# ETHERNET.net
KiCad netlist of a schematic drawn in Altium Designer
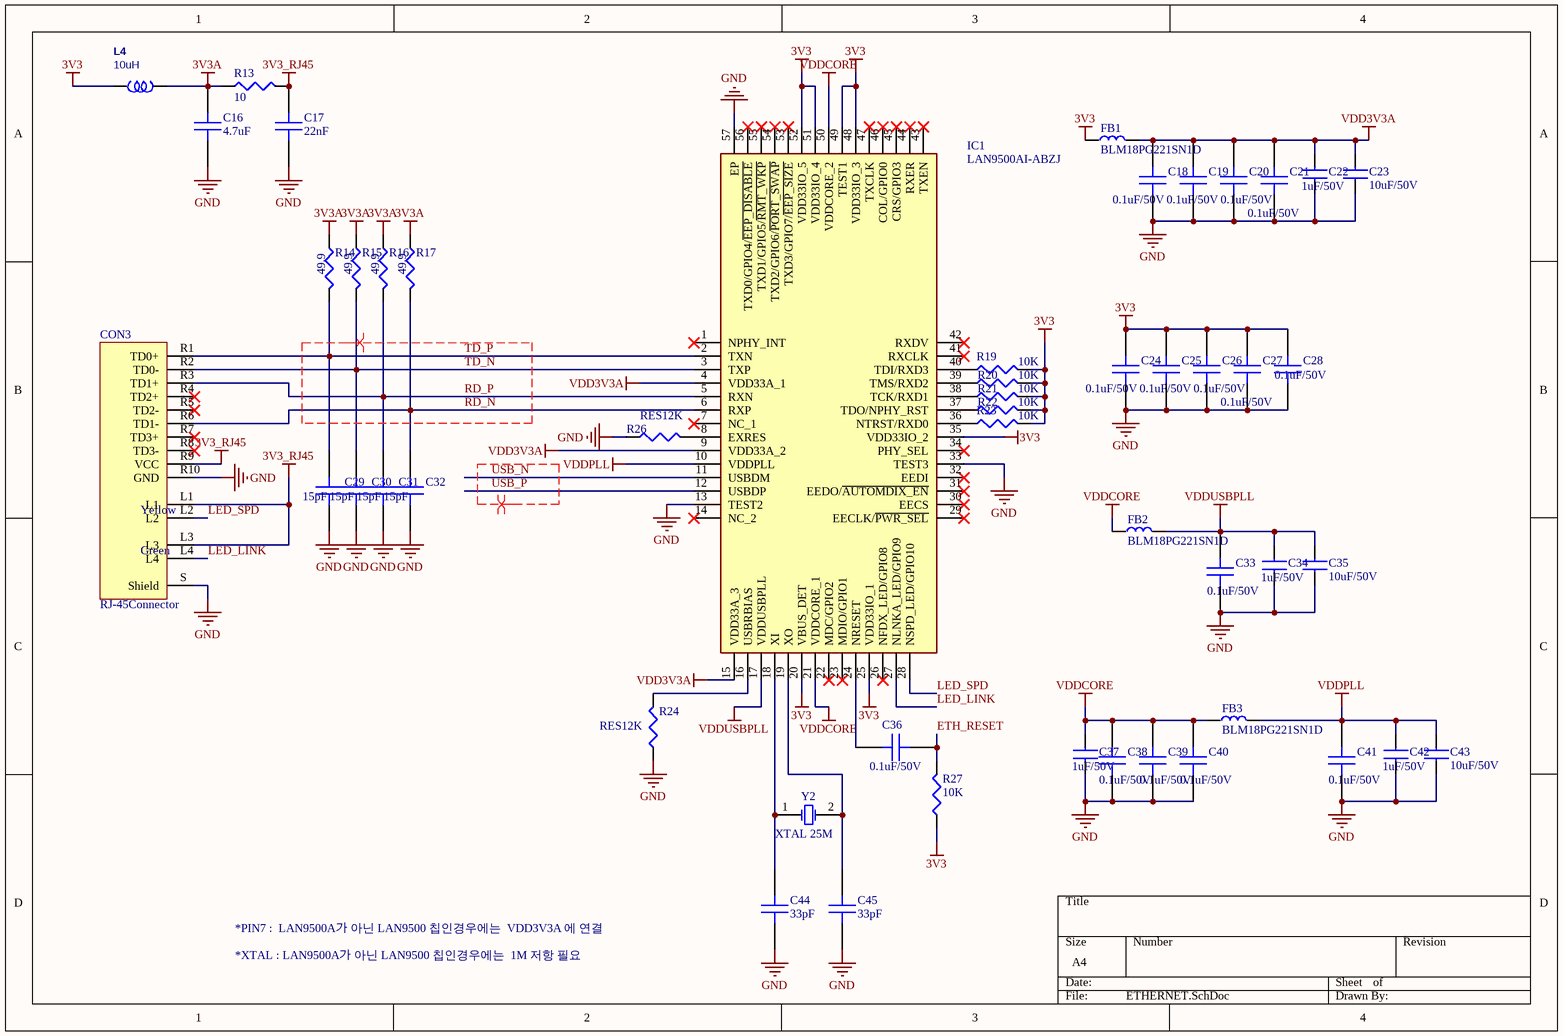
[diagram p0: ETHERNET.SchDoc]

(export (version "E")
  (design (tool "Eeschema 10.0.6"))
  (components
    (comp (ref "C16")
      (value "4.7uF")
      (footprint "CAP2.2u_0603")
      (description "CAP4.7u_0603")
      (libsource (lib "SensoMonitor") (part "CAP2.2u_0603"))
    )
    (comp (ref "C17")
      (value "22nF")
      (footprint "CAP2.2u_0603")
      (description "CAP22n_0603")
      (libsource (lib "SensoMonitor") (part "CAP2.2u_0603"))
    )
    (comp (ref "C18")
      (value "0.1uF/50V")
      (footprint "CAP0.1u_0603_ceramic")
      (description "cap, 0.1u 0603, 50V")
      (libsource (lib "MyLIB240624") (part "CAP0.1u_0603_ceramic"))
    )
    (comp (ref "C19")
      (value "0.1uF/50V")
      (footprint "CAP0.1u_0603_ceramic")
      (description "cap, 0.1u 0603, 50V")
      (libsource (lib "MyLIB240624") (part "CAP0.1u_0603_ceramic"))
    )
    (comp (ref "C20")
      (value "0.1uF/50V")
      (footprint "CAP0.1u_0603_ceramic")
      (description "cap, 0.1u 0603, 50V")
      (libsource (lib "MyLIB240624") (part "CAP0.1u_0603_ceramic"))
    )
    (comp (ref "C21")
      (value "0.1uF/50V")
      (footprint "CAP0.1u_0603_ceramic")
      (description "cap, 0.1u 0603, 50V")
      (libsource (lib "MyLIB240624") (part "CAP0.1u_0603_ceramic"))
    )
    (comp (ref "C22")
      (value "1uF/50V")
      (footprint "C-2012")
      (description "Capacitor, ceramic, 50V, 0805")
      (libsource (lib "MyLIB240624") (part "Cap1_1"))
    )
    (comp (ref "C23")
      (value "10uF/50V")
      (footprint "C-2012")
      (description "Capacitor, ceramic, 50V, 1206")
      (libsource (lib "MyLIB240624") (part "Cap1_1"))
    )
    (comp (ref "C24")
      (value "0.1uF/50V")
      (footprint "CAP0.1u_0603_ceramic")
      (description "cap, 0.1u 0603, 50V")
      (libsource (lib "MyLIB240624") (part "CAP0.1u_0603_ceramic"))
    )
    (comp (ref "C25")
      (value "0.1uF/50V")
      (footprint "CAP0.1u_0603_ceramic")
      (description "cap, 0.1u 0603, 50V")
      (libsource (lib "MyLIB240624") (part "CAP0.1u_0603_ceramic"))
    )
    (comp (ref "C26")
      (value "0.1uF/50V")
      (footprint "CAP0.1u_0603_ceramic")
      (description "cap, 0.1u 0603, 50V")
      (libsource (lib "MyLIB240624") (part "CAP0.1u_0603_ceramic"))
    )
    (comp (ref "C27")
      (value "0.1uF/50V")
      (footprint "CAP0.1u_0603_ceramic")
      (description "cap, 0.1u 0603, 50V")
      (libsource (lib "MyLIB240624") (part "CAP0.1u_0603_ceramic"))
    )
    (comp (ref "C28")
      (value "0.1uF/50V")
      (footprint "CAP0.1u_0603_ceramic")
      (description "cap, 0.1u 0603, 50V")
      (libsource (lib "MyLIB240624") (part "CAP0.1u_0603_ceramic"))
    )
    (comp (ref "C29")
      (value "15pF")
      (footprint "CAP2.2u_0603")
      (description "CAP15pF_0603")
      (libsource (lib "SensoMonitor") (part "CAP2.2u_0603"))
    )
    (comp (ref "C30")
      (value "15pF")
      (footprint "CAP2.2u_0603")
      (description "CAP15pF_0603")
      (libsource (lib "SensoMonitor") (part "CAP2.2u_0603"))
    )
    (comp (ref "C31")
      (value "15pF")
      (footprint "CAP2.2u_0603")
      (description "CAP15pF_0603")
      (libsource (lib "SensoMonitor") (part "CAP2.2u_0603"))
    )
    (comp (ref "C32")
      (value "15pF")
      (footprint "CAP2.2u_0603")
      (description "CAP15pF_0603")
      (libsource (lib "SensoMonitor") (part "CAP2.2u_0603"))
    )
    (comp (ref "C33")
      (value "0.1uF/50V")
      (footprint "CAP0.1u_0603_ceramic")
      (description "cap, 0.1u 0603, 50V")
      (libsource (lib "MyLIB240624") (part "CAP0.1u_0603_ceramic"))
    )
    (comp (ref "C34")
      (value "1uF/50V")
      (footprint "C-2012")
      (description "Capacitor, ceramic, 50V, 0805")
      (libsource (lib "MyLIB240624") (part "Cap1_1"))
    )
    (comp (ref "C35")
      (value "10uF/50V")
      (footprint "C-2012")
      (description "Capacitor, ceramic, 50V, 1206")
      (libsource (lib "MyLIB240624") (part "Cap1_1"))
    )
    (comp (ref "C36")
      (value "0.1uF/50V")
      (footprint "CAP0.1u_0603_ceramic")
      (description "cap, 0.1u 0603, 50V")
      (libsource (lib "MyLIB240624") (part "CAP0.1u_0603_ceramic"))
    )
    (comp (ref "C37")
      (value "1uF/50V")
      (footprint "C-2012")
      (description "Capacitor, ceramic, 50V, 0805")
      (libsource (lib "MyLIB240624") (part "Cap1_1"))
    )
    (comp (ref "C38")
      (value "0.1uF/50V")
      (footprint "CAP0.1u_0603_ceramic")
      (description "cap, 0.1u 0603, 50V")
      (libsource (lib "MyLIB240624") (part "CAP0.1u_0603_ceramic"))
    )
    (comp (ref "C39")
      (value "0.1uF/50V")
      (footprint "CAP0.1u_0603_ceramic")
      (description "cap, 0.1u 0603, 50V")
      (libsource (lib "MyLIB240624") (part "CAP0.1u_0603_ceramic"))
    )
    (comp (ref "C40")
      (value "0.1uF/50V")
      (footprint "CAP0.1u_0603_ceramic")
      (description "cap, 0.1u 0603, 50V")
      (libsource (lib "MyLIB240624") (part "CAP0.1u_0603_ceramic"))
    )
    (comp (ref "C41")
      (value "0.1uF/50V")
      (footprint "CAP0.1u_0603_ceramic")
      (description "cap, 0.1u 0603, 50V")
      (libsource (lib "MyLIB240624") (part "CAP0.1u_0603_ceramic"))
    )
    (comp (ref "C42")
      (value "1uF/50V")
      (footprint "C-2012")
      (description "Capacitor, ceramic, 50V, 0805")
      (libsource (lib "MyLIB240624") (part "Cap1_1"))
    )
    (comp (ref "C43")
      (value "10uF/50V")
      (footprint "C-2012")
      (description "Capacitor, ceramic, 50V, 1206")
      (libsource (lib "MyLIB240624") (part "Cap1_1"))
    )
    (comp (ref "C44")
      (value "33pF")
      (footprint "CAP33p_0603")
      (description "CAP33p_0603,ceramic")
      (libsource (lib "SensoMonitor") (part "CAP33p_0603"))
    )
    (comp (ref "C45")
      (value "33pF")
      (footprint "CAP33p_0603")
      (description "CAP33p_0603,ceramic")
      (libsource (lib "SensoMonitor") (part "CAP33p_0603"))
    )
    (comp (ref "CON3")
      (value "RJ-45Connector")
      (footprint "[RJ45]24G-1835GYD2NL")
      (description "[RJ-45] 24G-1835GYD2NL")
      (libsource (lib "SensoMonitor") (part "[RJ45]24G-1835GYD2NL"))
    )
    (comp (ref "FB1")
      (value "BLM18PG221SN1D")
      (footprint "BLM18PG221SN1D")
      (description "Ferrite Bead, BLM18PG221SN1D, 0603")
      (fields (field (name "MOUSER PART NUMBER") "81-BLM18PG221SN1D"))
      (libsource (lib "SensoMonitor") (part "BLM18PG221SN1D"))
    )
    (comp (ref "FB2")
      (value "BLM18PG221SN1D")
      (footprint "BLM18PG221SN1D")
      (description "Ferrite Bead, BLM18PG221SN1D, 0603")
      (fields (field (name "MOUSER PART NUMBER") "81-BLM18PG221SN1D"))
      (libsource (lib "SensoMonitor") (part "BLM18PG221SN1D"))
    )
    (comp (ref "FB3")
      (value "BLM18PG221SN1D")
      (footprint "BLM18PG221SN1D")
      (description "Ferrite Bead, BLM18PG221SN1D, 0603")
      (fields (field (name "MOUSER PART NUMBER") "81-BLM18PG221SN1D"))
      (libsource (lib "SensoMonitor") (part "BLM18PG221SN1D"))
    )
    (comp (ref "IC1")
      (value "LAN9500AI-ABZJ")
      (footprint "LAN9500AI-ABZJ")
      (description "Integrated Circuit, LAN9500AI-ABZJ, Microchip")
      (fields (field (name "MOUSER PART NUMBER") "886-LAN9500AI-ABZJ"))
      (libsource (lib "SensoMonitor") (part "LAN9500AI-ABZJ"))
    )
    (comp (ref "L4")
      (value "10uH")
      (footprint "IND10uCoil")
      (description "10uH(2012)")
      (libsource (lib "SensoMonitor") (part "IND10uCoil"))
    )
    (comp (ref "R13")
      (value "10")
      (footprint "RES20K_0603")
      (description "RES10_0603")
      (libsource (lib "SensoMonitor") (part "RES20K"))
    )
    (comp (ref "R14")
      (value "49.9")
      (footprint "RES20K_0603")
      (description "RES49.9_0603")
      (libsource (lib "SensoMonitor") (part "RES20K"))
    )
    (comp (ref "R15")
      (value "49.9")
      (footprint "RES20K_0603")
      (description "RES49.9_0603")
      (libsource (lib "SensoMonitor") (part "RES20K"))
    )
    (comp (ref "R16")
      (value "49.9")
      (footprint "RES20K_0603")
      (description "RES49.9_0603")
      (libsource (lib "SensoMonitor") (part "RES20K"))
    )
    (comp (ref "R17")
      (value "49.9")
      (footprint "RES20K_0603")
      (description "RES49.9_0603")
      (libsource (lib "SensoMonitor") (part "RES20K"))
    )
    (comp (ref "R19")
      (value "10K")
      (footprint "RES20K_0603")
      (description "RES10K_0603")
      (libsource (lib "SensoMonitor") (part "RES20K"))
    )
    (comp (ref "R20")
      (value "10K")
      (footprint "RES20K_0603")
      (description "RES10K_0603")
      (libsource (lib "SensoMonitor") (part "RES20K"))
    )
    (comp (ref "R21")
      (value "10K")
      (footprint "RES20K_0603")
      (description "RES10K_0603")
      (libsource (lib "SensoMonitor") (part "RES20K"))
    )
    (comp (ref "R22")
      (value "10K")
      (footprint "RES20K_0603")
      (description "RES10K_0603")
      (libsource (lib "SensoMonitor") (part "RES20K"))
    )
    (comp (ref "R23")
      (value "10K")
      (footprint "RES20K_0603")
      (description "RES10K_0603")
      (libsource (lib "SensoMonitor") (part "RES20K"))
    )
    (comp (ref "R24")
      (value "RES12K")
      (footprint "RES20K_0603")
      (description "RES12K_0603,1%")
      (libsource (lib "SensoMonitor") (part "RES20K"))
    )
    (comp (ref "R26")
      (value "RES12K")
      (footprint "RES20K_0603")
      (description "RES12K_0603,1%")
      (libsource (lib "SensoMonitor") (part "RES20K"))
    )
    (comp (ref "R27")
      (value "10K")
      (footprint "RES20K_0603")
      (description "RES10K_0603")
      (libsource (lib "SensoMonitor") (part "RES20K"))
    )
    (comp (ref "Y2")
      (value "XTAL 25M")
      (footprint "XTAL_SMD_8M")
      (libsource (lib "MyLIB240624") (part "XTAL8M"))
    )
  )
  (nets
    (net (code "1") (name "/ETH_RESET") (class "Default")
      (node (ref "C36") (pin "1") (pinfunction "1_1") (pintype "passive"))
      (node (ref "R27") (pin "2") (pinfunction "2_2") (pintype "passive"))
    )
    (net (code "2") (name "/LED_LINK") (class "Default")
      (node (ref "CON3") (pin "L4") (pinfunction "L4_L4") (pintype "passive"))
      (node (ref "IC1") (pin "27") (pinfunction "NLNKA_LED/GPIO9_27") (pintype "passive"))
    )
    (net (code "3") (name "/LED_SPD") (class "Default")
      (node (ref "CON3") (pin "L2") (pinfunction "L2_L2") (pintype "passive"))
      (node (ref "IC1") (pin "28") (pinfunction "NSPD_LED/GPIO10_28") (pintype "passive"))
    )
    (net (code "4") (name "/RD_N") (class "Default")
      (node (ref "C32") (pin "2") (pinfunction "2_2") (pintype "passive"))
      (node (ref "CON3") (pin "R6") (pinfunction "TD1-_R6") (pintype "passive"))
      (node (ref "IC1") (pin "6") (pinfunction "RXP_6") (pintype "passive"))
      (node (ref "R17") (pin "2") (pinfunction "2_2") (pintype "passive"))
    )
    (net (code "5") (name "/RD_P") (class "Default")
      (node (ref "C31") (pin "2") (pinfunction "2_2") (pintype "passive"))
      (node (ref "CON3") (pin "R3") (pinfunction "TD1+_R3") (pintype "passive"))
      (node (ref "IC1") (pin "5") (pinfunction "RXN_5") (pintype "passive"))
      (node (ref "R16") (pin "2") (pinfunction "2_2") (pintype "passive"))
    )
    (net (code "6") (name "/TD_N") (class "Default")
      (node (ref "C30") (pin "2") (pinfunction "2_2") (pintype "passive"))
      (node (ref "CON3") (pin "R2") (pinfunction "TD0-_R2") (pintype "passive"))
      (node (ref "IC1") (pin "3") (pinfunction "TXP_3") (pintype "passive"))
      (node (ref "R15") (pin "2") (pinfunction "2_2") (pintype "passive"))
    )
    (net (code "7") (name "/TD_P") (class "Default")
      (node (ref "C29") (pin "2") (pinfunction "2_2") (pintype "passive"))
      (node (ref "CON3") (pin "R1") (pinfunction "TD0+_R1") (pintype "passive"))
      (node (ref "IC1") (pin "2") (pinfunction "TXN_2") (pintype "passive"))
      (node (ref "R14") (pin "2") (pinfunction "2_2") (pintype "passive"))
    )
    (net (code "8") (name "/USB_N") (class "Default")
      (node (ref "IC1") (pin "11") (pinfunction "USBDM_11") (pintype "passive"))
    )
    (net (code "9") (name "/USB_P") (class "Default")
      (node (ref "IC1") (pin "12") (pinfunction "USBDP_12") (pintype "passive"))
    )
    (net (code "10") (name "3V3") (class "Default")
      (node (ref "C24") (pin "2") (pinfunction "2_2") (pintype "passive"))
      (node (ref "C25") (pin "2") (pinfunction "2_2") (pintype "passive"))
      (node (ref "C26") (pin "2") (pinfunction "2_2") (pintype "passive"))
      (node (ref "C27") (pin "2") (pinfunction "2_2") (pintype "passive"))
      (node (ref "C28") (pin "2") (pinfunction "2_2") (pintype "passive"))
      (node (ref "FB1") (pin "1") (pinfunction "1_1") (pintype "passive"))
      (node (ref "IC1") (pin "20") (pinfunction "VBUS_DET_20") (pintype "passive"))
      (node (ref "IC1") (pin "25") (pinfunction "VDD33IO_1_25") (pintype "passive"))
      (node (ref "IC1") (pin "35") (pinfunction "VDD33IO_2_35") (pintype "passive"))
      (node (ref "IC1") (pin "48") (pinfunction "VDD33IO_3_48") (pintype "passive"))
      (node (ref "IC1") (pin "49") (pinfunction "TEST1_49") (pintype "passive"))
      (node (ref "IC1") (pin "51") (pinfunction "VDD33IO_4_51") (pintype "passive"))
      (node (ref "IC1") (pin "52") (pinfunction "VDD33IO_5_52") (pintype "passive"))
      (node (ref "L4") (pin "2") (pintype "passive"))
      (node (ref "R19") (pin "2") (pinfunction "2_2") (pintype "passive"))
      (node (ref "R20") (pin "2") (pinfunction "2_2") (pintype "passive"))
      (node (ref "R21") (pin "2") (pinfunction "2_2") (pintype "passive"))
      (node (ref "R22") (pin "2") (pinfunction "2_2") (pintype "passive"))
      (node (ref "R23") (pin "2") (pinfunction "2_2") (pintype "passive"))
      (node (ref "R27") (pin "1") (pinfunction "1_1") (pintype "passive"))
    )
    (net (code "11") (name "3V3A") (class "Default")
      (node (ref "C16") (pin "2") (pinfunction "2_2") (pintype "passive"))
      (node (ref "L4") (pin "1") (pintype "passive"))
      (node (ref "R13") (pin "1") (pinfunction "1_1") (pintype "passive"))
      (node (ref "R14") (pin "1") (pinfunction "1_1") (pintype "passive"))
      (node (ref "R15") (pin "1") (pinfunction "1_1") (pintype "passive"))
      (node (ref "R16") (pin "1") (pinfunction "1_1") (pintype "passive"))
      (node (ref "R17") (pin "1") (pinfunction "1_1") (pintype "passive"))
    )
    (net (code "12") (name "3V3_RJ45") (class "Default")
      (node (ref "C17") (pin "2") (pinfunction "2_2") (pintype "passive"))
      (node (ref "CON3") (pin "L1") (pinfunction "L1_L1") (pintype "passive"))
      (node (ref "CON3") (pin "L3") (pinfunction "L3_L3") (pintype "passive"))
      (node (ref "CON3") (pin "R9") (pinfunction "VCC_R9") (pintype "passive"))
      (node (ref "R13") (pin "2") (pinfunction "2_2") (pintype "passive"))
    )
    (net (code "13") (name "GND") (class "Default")
      (node (ref "C16") (pin "1") (pinfunction "1_1") (pintype "passive"))
      (node (ref "C17") (pin "1") (pinfunction "1_1") (pintype "passive"))
      (node (ref "C18") (pin "1") (pinfunction "1_1") (pintype "passive"))
      (node (ref "C19") (pin "1") (pinfunction "1_1") (pintype "passive"))
      (node (ref "C20") (pin "1") (pinfunction "1_1") (pintype "passive"))
      (node (ref "C21") (pin "1") (pinfunction "1_1") (pintype "passive"))
      (node (ref "C22") (pin "2") (pintype "passive"))
      (node (ref "C23") (pin "2") (pintype "passive"))
      (node (ref "C24") (pin "1") (pinfunction "1_1") (pintype "passive"))
      (node (ref "C25") (pin "1") (pinfunction "1_1") (pintype "passive"))
      (node (ref "C26") (pin "1") (pinfunction "1_1") (pintype "passive"))
      (node (ref "C27") (pin "1") (pinfunction "1_1") (pintype "passive"))
      (node (ref "C28") (pin "1") (pinfunction "1_1") (pintype "passive"))
      (node (ref "C29") (pin "1") (pinfunction "1_1") (pintype "passive"))
      (node (ref "C30") (pin "1") (pinfunction "1_1") (pintype "passive"))
      (node (ref "C31") (pin "1") (pinfunction "1_1") (pintype "passive"))
      (node (ref "C32") (pin "1") (pinfunction "1_1") (pintype "passive"))
      (node (ref "C33") (pin "1") (pinfunction "1_1") (pintype "passive"))
      (node (ref "C34") (pin "2") (pintype "passive"))
      (node (ref "C35") (pin "2") (pintype "passive"))
      (node (ref "C37") (pin "2") (pintype "passive"))
      (node (ref "C38") (pin "1") (pinfunction "1_1") (pintype "passive"))
      (node (ref "C39") (pin "1") (pinfunction "1_1") (pintype "passive"))
      (node (ref "C40") (pin "1") (pinfunction "1_1") (pintype "passive"))
      (node (ref "C41") (pin "1") (pinfunction "1_1") (pintype "passive"))
      (node (ref "C42") (pin "2") (pintype "passive"))
      (node (ref "C43") (pin "2") (pintype "passive"))
      (node (ref "C44") (pin "1") (pinfunction "1_1") (pintype "passive"))
      (node (ref "C45") (pin "1") (pinfunction "1_1") (pintype "passive"))
      (node (ref "CON3") (pin "R10") (pinfunction "GND_R10") (pintype "passive"))
      (node (ref "CON3") (pin "S") (pinfunction "Shield_S") (pintype "passive"))
      (node (ref "IC1") (pin "13") (pinfunction "TEST2_13") (pintype "passive"))
      (node (ref "IC1") (pin "33") (pinfunction "TEST3_33") (pintype "passive"))
      (node (ref "IC1") (pin "57") (pinfunction "EP_57") (pintype "passive"))
      (node (ref "R24") (pin "1") (pinfunction "1_1") (pintype "passive"))
      (node (ref "R26") (pin "1") (pinfunction "1_1") (pintype "passive"))
    )
    (net (code "14") (name "Net-(IC1-EXRES)") (class "Default")
      (node (ref "IC1") (pin "8") (pinfunction "EXRES_8") (pintype "passive"))
      (node (ref "R26") (pin "2") (pinfunction "2_2") (pintype "passive"))
    )
    (net (code "15") (name "Net-(IC1-NRESET)") (class "Default")
      (node (ref "C36") (pin "2") (pinfunction "2_2") (pintype "passive"))
      (node (ref "IC1") (pin "24") (pinfunction "NRESET_24") (pintype "passive"))
    )
    (net (code "16") (name "Net-(IC1-NTRST{slash}RXD0)") (class "Default")
      (node (ref "IC1") (pin "36") (pinfunction "NTRST/RXD0_36") (pintype "passive"))
      (node (ref "R23") (pin "1") (pinfunction "1_1") (pintype "passive"))
    )
    (net (code "17") (name "Net-(IC1-TCK{slash}RXD1)") (class "Default")
      (node (ref "IC1") (pin "38") (pinfunction "TCK/RXD1_38") (pintype "passive"))
      (node (ref "R21") (pin "1") (pinfunction "1_1") (pintype "passive"))
    )
    (net (code "18") (name "Net-(IC1-TDI{slash}RXD3)") (class "Default")
      (node (ref "IC1") (pin "40") (pinfunction "TDI/RXD3_40") (pintype "passive"))
      (node (ref "R19") (pin "1") (pinfunction "1_1") (pintype "passive"))
    )
    (net (code "19") (name "Net-(IC1-TDO{slash}NPHY_RST)") (class "Default")
      (node (ref "IC1") (pin "37") (pinfunction "TDO/NPHY_RST_37") (pintype "passive"))
      (node (ref "R22") (pin "1") (pinfunction "1_1") (pintype "passive"))
    )
    (net (code "20") (name "Net-(IC1-TMS{slash}RXD2)") (class "Default")
      (node (ref "IC1") (pin "39") (pinfunction "TMS/RXD2_39") (pintype "passive"))
      (node (ref "R20") (pin "1") (pinfunction "1_1") (pintype "passive"))
    )
    (net (code "21") (name "Net-(IC1-USBRBIAS)") (class "Default")
      (node (ref "IC1") (pin "16") (pinfunction "USBRBIAS_16") (pintype "passive"))
      (node (ref "R24") (pin "2") (pinfunction "2_2") (pintype "passive"))
    )
    (net (code "22") (name "Net-(IC1-XI)") (class "Default")
      (node (ref "C44") (pin "2") (pinfunction "2_2") (pintype "passive"))
      (node (ref "IC1") (pin "18") (pinfunction "XI_18") (pintype "passive"))
      (node (ref "Y2") (pin "1") (pinfunction "OSC1_1") (pintype "passive"))
    )
    (net (code "23") (name "Net-(IC1-XO)") (class "Default")
      (node (ref "C45") (pin "2") (pinfunction "2_2") (pintype "passive"))
      (node (ref "IC1") (pin "19") (pinfunction "XO_19") (pintype "passive"))
      (node (ref "Y2") (pin "2") (pinfunction "OSC2_2") (pintype "passive"))
    )
    (net (code "24") (name "VDD3V3A") (class "Default")
      (node (ref "C18") (pin "2") (pinfunction "2_2") (pintype "passive"))
      (node (ref "C19") (pin "2") (pinfunction "2_2") (pintype "passive"))
      (node (ref "C20") (pin "2") (pinfunction "2_2") (pintype "passive"))
      (node (ref "C21") (pin "2") (pinfunction "2_2") (pintype "passive"))
      (node (ref "C22") (pin "1") (pintype "passive"))
      (node (ref "C23") (pin "1") (pintype "passive"))
      (node (ref "FB1") (pin "2") (pinfunction "2_2") (pintype "passive"))
      (node (ref "IC1") (pin "15") (pinfunction "VDD33A_3_15") (pintype "passive"))
      (node (ref "IC1") (pin "4") (pinfunction "VDD33A_1_4") (pintype "passive"))
      (node (ref "IC1") (pin "9") (pinfunction "VDD33A_2_9") (pintype "passive"))
    )
    (net (code "25") (name "VDDCORE") (class "Default")
      (node (ref "C37") (pin "1") (pintype "passive"))
      (node (ref "C38") (pin "2") (pinfunction "2_2") (pintype "passive"))
      (node (ref "C39") (pin "2") (pinfunction "2_2") (pintype "passive"))
      (node (ref "C40") (pin "2") (pinfunction "2_2") (pintype "passive"))
      (node (ref "FB2") (pin "1") (pinfunction "1_1") (pintype "passive"))
      (node (ref "FB3") (pin "1") (pinfunction "1_1") (pintype "passive"))
      (node (ref "IC1") (pin "21") (pinfunction "VDDCORE_1_21") (pintype "passive"))
      (node (ref "IC1") (pin "50") (pinfunction "VDDCORE_2_50") (pintype "passive"))
    )
    (net (code "26") (name "VDDPLL") (class "Default")
      (node (ref "C41") (pin "2") (pinfunction "2_2") (pintype "passive"))
      (node (ref "C42") (pin "1") (pintype "passive"))
      (node (ref "C43") (pin "1") (pintype "passive"))
      (node (ref "FB3") (pin "2") (pinfunction "2_2") (pintype "passive"))
      (node (ref "IC1") (pin "10") (pinfunction "VDDPLL_10") (pintype "passive"))
    )
    (net (code "27") (name "VDDUSBPLL") (class "Default")
      (node (ref "C33") (pin "2") (pinfunction "2_2") (pintype "passive"))
      (node (ref "C34") (pin "1") (pintype "passive"))
      (node (ref "C35") (pin "1") (pintype "passive"))
      (node (ref "FB2") (pin "2") (pinfunction "2_2") (pintype "passive"))
      (node (ref "IC1") (pin "17") (pinfunction "VDDUSBPLL_17") (pintype "passive"))
    )
    (net (code "28") (name "unconnected-(CON3-TD2+-PadR4)") (class "Default")
      (node (ref "CON3") (pin "R4") (pinfunction "TD2+_R4") (pintype "passive+no_connect"))
    )
    (net (code "29") (name "unconnected-(CON3-TD2--PadR5)") (class "Default")
      (node (ref "CON3") (pin "R5") (pinfunction "TD2-_R5") (pintype "passive+no_connect"))
    )
    (net (code "30") (name "unconnected-(CON3-TD3+-PadR7)") (class "Default")
      (node (ref "CON3") (pin "R7") (pinfunction "TD3+_R7") (pintype "passive+no_connect"))
    )
    (net (code "31") (name "unconnected-(CON3-TD3--PadR8)") (class "Default")
      (node (ref "CON3") (pin "R8") (pinfunction "TD3-_R8") (pintype "passive+no_connect"))
    )
    (net (code "32") (name "unconnected-(IC1-COL{slash}GPIO0-Pad46)") (class "Default")
      (node (ref "IC1") (pin "46") (pinfunction "COL/GPIO0_46") (pintype "passive+no_connect"))
    )
    (net (code "33") (name "unconnected-(IC1-CRS{slash}GPIO3-Pad45)") (class "Default")
      (node (ref "IC1") (pin "45") (pinfunction "CRS/GPIO3_45") (pintype "passive+no_connect"))
    )
    (net (code "34") (name "unconnected-(IC1-EECLK{slash}~{PWR_SEL}-Pad29)") (class "Default")
      (node (ref "IC1") (pin "29") (pinfunction "EECLK/~{PWR_SEL}_29") (pintype "passive+no_connect"))
    )
    (net (code "35") (name "unconnected-(IC1-EECS-Pad30)") (class "Default")
      (node (ref "IC1") (pin "30") (pinfunction "EECS_30") (pintype "passive+no_connect"))
    )
    (net (code "36") (name "unconnected-(IC1-EEDI-Pad32)") (class "Default")
      (node (ref "IC1") (pin "32") (pinfunction "EEDI_32") (pintype "passive+no_connect"))
    )
    (net (code "37") (name "unconnected-(IC1-EEDO{slash}~{AUTOMDIX_EN}-Pad31)") (class "Default")
      (node (ref "IC1") (pin "31") (pinfunction "EEDO/~{AUTOMDIX_EN}_31") (pintype "passive+no_connect"))
    )
    (net (code "38") (name "unconnected-(IC1-MDC{slash}GPIO2-Pad22)") (class "Default")
      (node (ref "IC1") (pin "22") (pinfunction "MDC/GPIO2_22") (pintype "passive+no_connect"))
    )
    (net (code "39") (name "unconnected-(IC1-MDIO{slash}GPIO1-Pad23)") (class "Default")
      (node (ref "IC1") (pin "23") (pinfunction "MDIO/GPIO1_23") (pintype "passive+no_connect"))
    )
    (net (code "40") (name "unconnected-(IC1-NC_1-Pad7)") (class "Default")
      (node (ref "IC1") (pin "7") (pinfunction "NC_1_7") (pintype "passive+no_connect"))
    )
    (net (code "41") (name "unconnected-(IC1-NC_2-Pad14)") (class "Default")
      (node (ref "IC1") (pin "14") (pinfunction "NC_2_14") (pintype "passive+no_connect"))
    )
    (net (code "42") (name "unconnected-(IC1-NFDX_LED{slash}GPIO8-Pad26)") (class "Default")
      (node (ref "IC1") (pin "26") (pinfunction "NFDX_LED/GPIO8_26") (pintype "passive+no_connect"))
    )
    (net (code "43") (name "unconnected-(IC1-NPHY_INT-Pad1)") (class "Default")
      (node (ref "IC1") (pin "1") (pinfunction "NPHY_INT_1") (pintype "passive+no_connect"))
    )
    (net (code "44") (name "unconnected-(IC1-PHY_SEL-Pad34)") (class "Default")
      (node (ref "IC1") (pin "34") (pinfunction "PHY_SEL_34") (pintype "passive+no_connect"))
    )
    (net (code "45") (name "unconnected-(IC1-RXCLK-Pad41)") (class "Default")
      (node (ref "IC1") (pin "41") (pinfunction "RXCLK_41") (pintype "passive+no_connect"))
    )
    (net (code "46") (name "unconnected-(IC1-RXDV-Pad42)") (class "Default")
      (node (ref "IC1") (pin "42") (pinfunction "RXDV_42") (pintype "passive+no_connect"))
    )
    (net (code "47") (name "unconnected-(IC1-RXER-Pad44)") (class "Default")
      (node (ref "IC1") (pin "44") (pinfunction "RXER_44") (pintype "passive+no_connect"))
    )
    (net (code "48") (name "unconnected-(IC1-TXCLK-Pad47)") (class "Default")
      (node (ref "IC1") (pin "47") (pinfunction "TXCLK_47") (pintype "passive+no_connect"))
    )
    (net (code "49") (name "unconnected-(IC1-TXD0{slash}GPIO4{slash}~{EEP_DISABLE}-Pad56)") (class "Default")
      (node (ref "IC1") (pin "56") (pinfunction "TXD0/GPIO4/~{EEP_DISABLE}_56") (pintype "passive+no_connect"))
    )
    (net (code "50") (name "unconnected-(IC1-TXD1{slash}GPIO5{slash}~{RMT_WKP}-Pad55)") (class "Default")
      (node (ref "IC1") (pin "55") (pinfunction "TXD1/GPIO5/~{RMT_WKP}_55") (pintype "passive+no_connect"))
    )
    (net (code "51") (name "unconnected-(IC1-TXD2{slash}GPIO6{slash}~{PORT_SWAP}-Pad54)") (class "Default")
      (node (ref "IC1") (pin "54") (pinfunction "TXD2/GPIO6/~{PORT_SWAP}_54") (pintype "passive+no_connect"))
    )
    (net (code "52") (name "unconnected-(IC1-TXD3{slash}GPIO7{slash}~{EEP_SIZE}-Pad53)") (class "Default")
      (node (ref "IC1") (pin "53") (pinfunction "TXD3/GPIO7/~{EEP_SIZE}_53") (pintype "passive+no_connect"))
    )
    (net (code "53") (name "unconnected-(IC1-TXEN-Pad43)") (class "Default")
      (node (ref "IC1") (pin "43") (pinfunction "TXEN_43") (pintype "passive+no_connect"))
    )
  )
)
